# Cart64out_0a.net
KiCad netlist of a schematic drawn in EAGLE
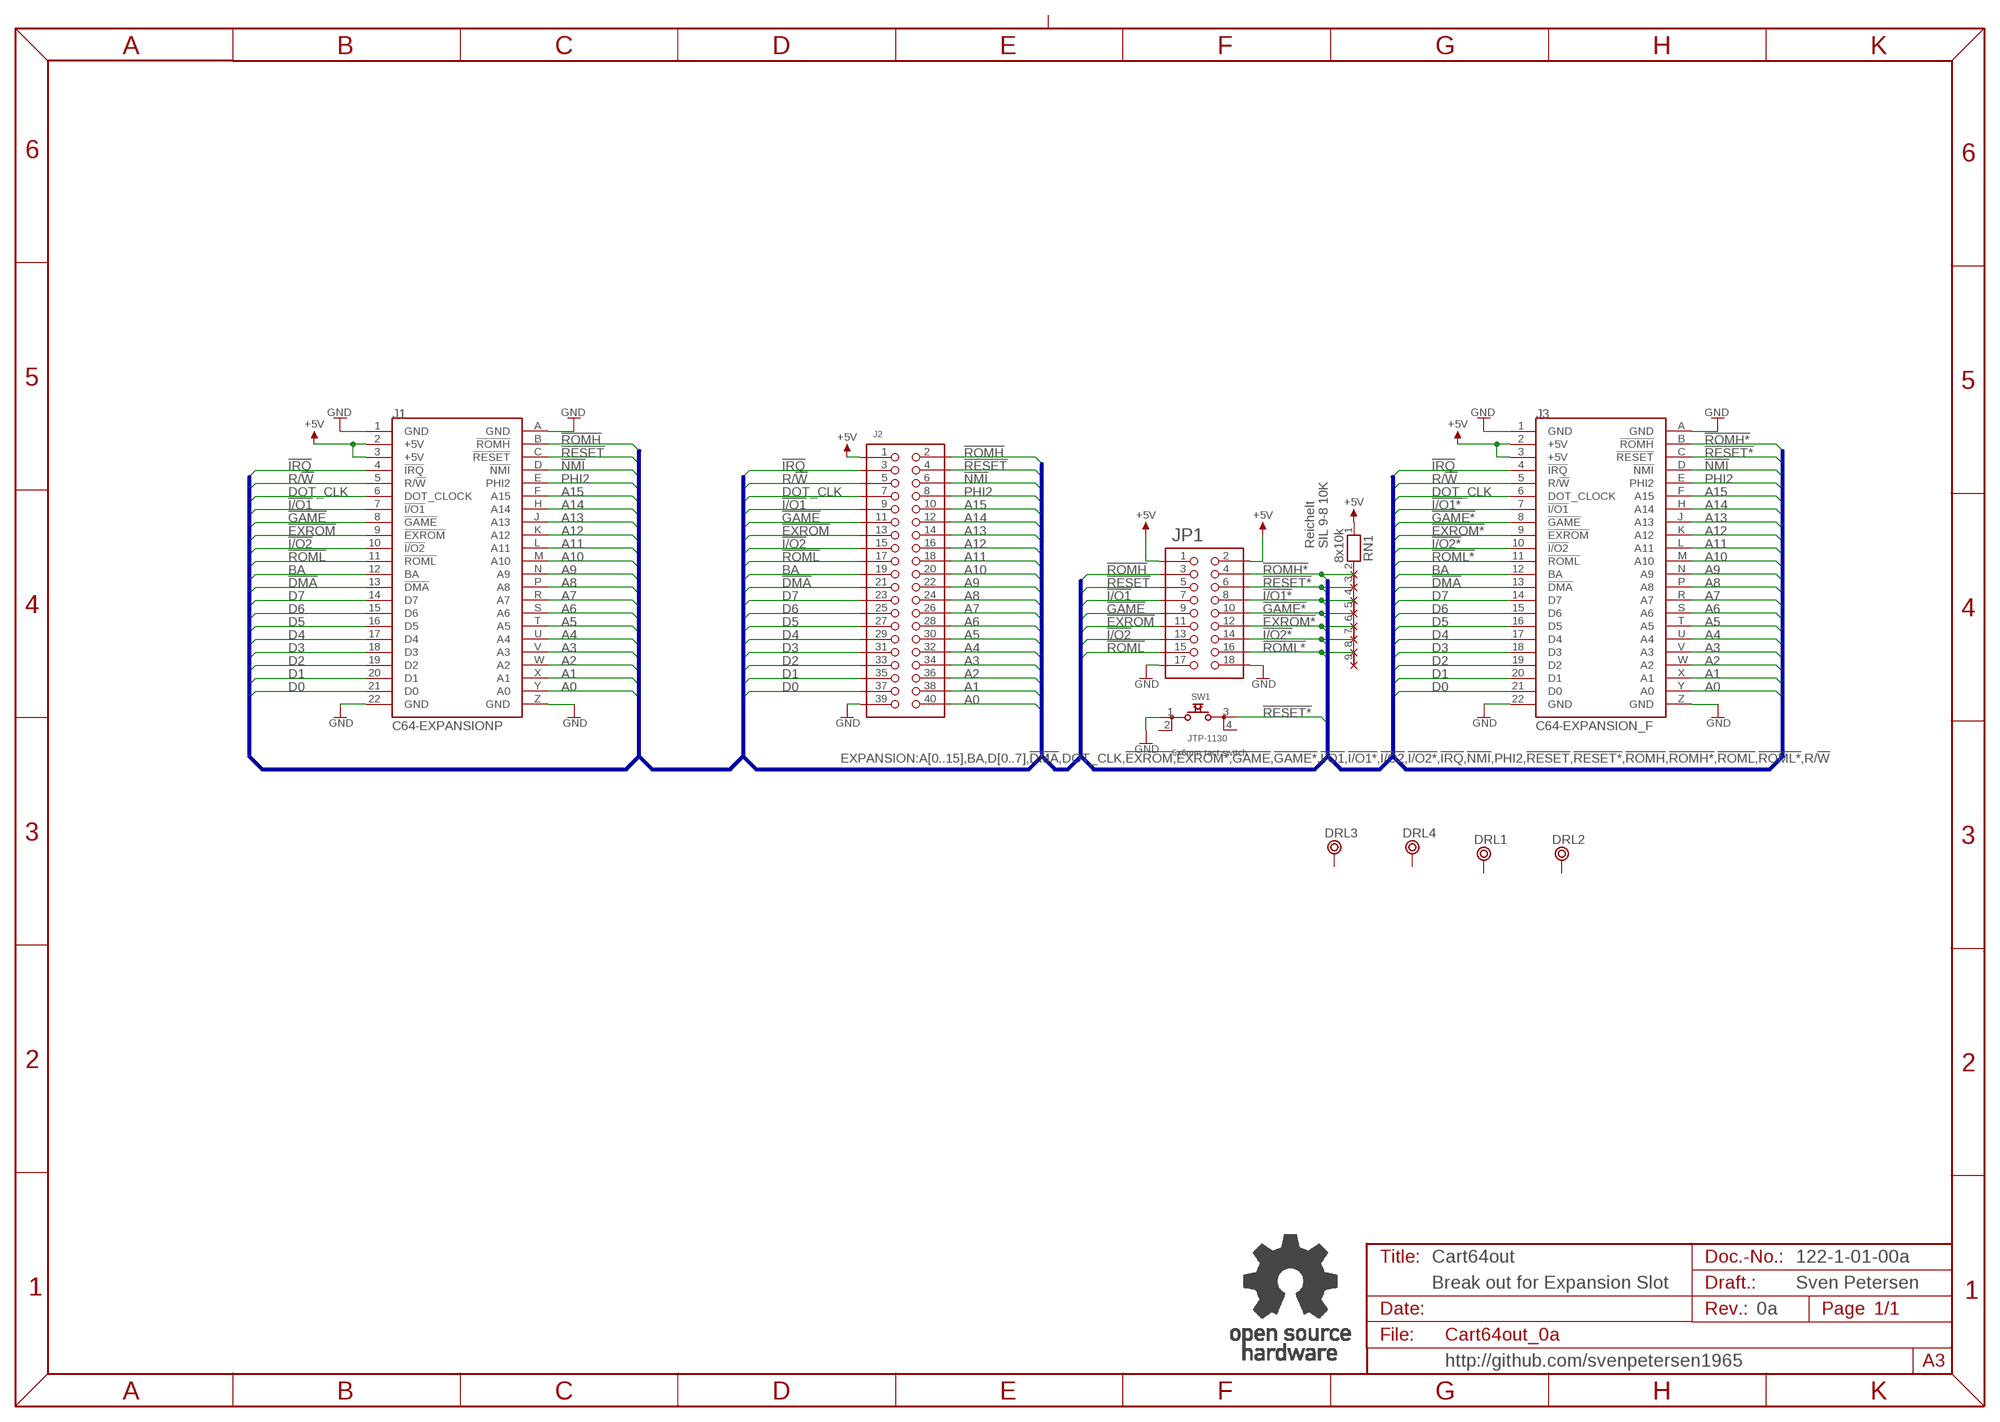
[diagram p0: schematic, sheet 1]

(export (version "E")
  (design (tool "Eeschema 10.0.6"))
  (components
    (comp (ref "DRL1")
      (value "BOHR3,3")
      (footprint "eagle-import:BOHR3,3")
      (libsource (lib "eagle-import") (part "BOHR3,3"))
    )
    (comp (ref "DRL2")
      (value "BOHR3,3")
      (footprint "eagle-import:BOHR3,3")
      (libsource (lib "eagle-import") (part "BOHR3,3"))
    )
    (comp (ref "DRL3")
      (value "BOHR3,3")
      (footprint "eagle-import:BOHR3,3")
      (libsource (lib "eagle-import") (part "BOHR3,3"))
    )
    (comp (ref "DRL4")
      (value "BOHR3,3")
      (footprint "eagle-import:BOHR3,3")
      (libsource (lib "eagle-import") (part "BOHR3,3"))
    )
    (comp (ref "J1")
      (value "C64-EXPANSIONP")
      (footprint "eagle-import:EXPPORT")
      (libsource (lib "eagle-import") (part "C64-EXPANSIONP"))
    )
    (comp (ref "J2")
      (value "PINHD-2X20WV")
      (footprint "eagle-import:2X20WV")
      (libsource (lib "eagle-import") (part "PINHD-2X20WV"))
    )
    (comp (ref "J3")
      (value "C64-EXPANSION_F")
      (footprint "eagle-import:EXPANSION_OUT")
      (libsource (lib "eagle-import") (part "C64-EXPANSION_F"))
    )
    (comp (ref "JP1")
      (value "PINHD-2X9")
      (footprint "eagle-import:2X09")
      (libsource (lib "eagle-import") (part "PINHD-2X9"))
    )
    (comp (ref "RN1")
      (value "8x10k")
      (footprint "eagle-import:RN-9")
      (libsource (lib "eagle-import") (part "RN08"))
    )
    (comp (ref "SW1")
      (value "JTP-1130")
      (footprint "eagle-import:JTP-1130")
      (libsource (lib "eagle-import") (part "JTP-1130"))
    )
    (comp (ref "U$22")
      (value "OPEN_SOURCE_HW")
      (footprint "eagle-import:OPENHW")
      (libsource (lib "eagle-import") (part "OPEN_SOURCE_HW"))
    )
  )
  (nets
    (net (code "1") (name "+5V") (class "Default")
      (node (ref "J1") (pin "2") (pinfunction "+5V_2") (pintype "power_in"))
      (node (ref "J1") (pin "3") (pinfunction "+5V_3") (pintype "power_in"))
      (node (ref "J2") (pin "1") (pinfunction "1_1") (pintype "passive"))
      (node (ref "J3") (pin "2") (pinfunction "+5V_2") (pintype "power_in"))
      (node (ref "J3") (pin "3") (pinfunction "+5V_3") (pintype "power_in"))
      (node (ref "JP1") (pin "1") (pinfunction "1_1") (pintype "passive"))
      (node (ref "JP1") (pin "2") (pinfunction "2_2") (pintype "passive"))
      (node (ref "RN1") (pin "1") (pinfunction "1_1") (pintype "passive"))
    )
    (net (code "2") (name "/A0") (class "Default")
      (node (ref "J1") (pin "Y") (pinfunction "A0_Y") (pintype "bidirectional"))
      (node (ref "J2") (pin "40") (pinfunction "40_40") (pintype "passive"))
      (node (ref "J3") (pin "Y") (pinfunction "A0_Y") (pintype "bidirectional"))
    )
    (net (code "3") (name "/A1") (class "Default")
      (node (ref "J1") (pin "X") (pinfunction "A1_X") (pintype "bidirectional"))
      (node (ref "J2") (pin "38") (pinfunction "38_38") (pintype "passive"))
      (node (ref "J3") (pin "X") (pinfunction "A1_X") (pintype "bidirectional"))
    )
    (net (code "4") (name "/A2") (class "Default")
      (node (ref "J1") (pin "W") (pinfunction "A2_W") (pintype "bidirectional"))
      (node (ref "J2") (pin "36") (pinfunction "36_36") (pintype "passive"))
      (node (ref "J3") (pin "W") (pinfunction "A2_W") (pintype "bidirectional"))
    )
    (net (code "5") (name "/A3") (class "Default")
      (node (ref "J1") (pin "V") (pinfunction "A3_V") (pintype "bidirectional"))
      (node (ref "J2") (pin "34") (pinfunction "34_34") (pintype "passive"))
      (node (ref "J3") (pin "V") (pinfunction "A3_V") (pintype "bidirectional"))
    )
    (net (code "6") (name "/A4") (class "Default")
      (node (ref "J1") (pin "U") (pinfunction "A4_U") (pintype "bidirectional"))
      (node (ref "J2") (pin "32") (pinfunction "32_32") (pintype "passive"))
      (node (ref "J3") (pin "U") (pinfunction "A4_U") (pintype "bidirectional"))
    )
    (net (code "7") (name "/A5") (class "Default")
      (node (ref "J1") (pin "T") (pinfunction "A5_T") (pintype "bidirectional"))
      (node (ref "J2") (pin "30") (pinfunction "30_30") (pintype "passive"))
      (node (ref "J3") (pin "T") (pinfunction "A5_T") (pintype "bidirectional"))
    )
    (net (code "8") (name "/A6") (class "Default")
      (node (ref "J1") (pin "S") (pinfunction "A6_S") (pintype "bidirectional"))
      (node (ref "J2") (pin "28") (pinfunction "28_28") (pintype "passive"))
      (node (ref "J3") (pin "S") (pinfunction "A6_S") (pintype "bidirectional"))
    )
    (net (code "9") (name "/A7") (class "Default")
      (node (ref "J1") (pin "R") (pinfunction "A7_R") (pintype "bidirectional"))
      (node (ref "J2") (pin "26") (pinfunction "26_26") (pintype "passive"))
      (node (ref "J3") (pin "R") (pinfunction "A7_R") (pintype "bidirectional"))
    )
    (net (code "10") (name "/A8") (class "Default")
      (node (ref "J1") (pin "P") (pinfunction "A8_P") (pintype "bidirectional"))
      (node (ref "J2") (pin "24") (pinfunction "24_24") (pintype "passive"))
      (node (ref "J3") (pin "P") (pinfunction "A8_P") (pintype "bidirectional"))
    )
    (net (code "11") (name "/A9") (class "Default")
      (node (ref "J1") (pin "N") (pinfunction "A9_N") (pintype "bidirectional"))
      (node (ref "J2") (pin "22") (pinfunction "22_22") (pintype "passive"))
      (node (ref "J3") (pin "N") (pinfunction "A9_N") (pintype "bidirectional"))
    )
    (net (code "12") (name "/A10") (class "Default")
      (node (ref "J1") (pin "M") (pinfunction "A10_M") (pintype "bidirectional"))
      (node (ref "J2") (pin "20") (pinfunction "20_20") (pintype "passive"))
      (node (ref "J3") (pin "M") (pinfunction "A10_M") (pintype "bidirectional"))
    )
    (net (code "13") (name "/A11") (class "Default")
      (node (ref "J1") (pin "L") (pinfunction "A11_L") (pintype "bidirectional"))
      (node (ref "J2") (pin "18") (pinfunction "18_18") (pintype "passive"))
      (node (ref "J3") (pin "L") (pinfunction "A11_L") (pintype "bidirectional"))
    )
    (net (code "14") (name "/A12") (class "Default")
      (node (ref "J1") (pin "K") (pinfunction "A12_K") (pintype "bidirectional"))
      (node (ref "J2") (pin "16") (pinfunction "16_16") (pintype "passive"))
      (node (ref "J3") (pin "K") (pinfunction "A12_K") (pintype "bidirectional"))
    )
    (net (code "15") (name "/A13") (class "Default")
      (node (ref "J1") (pin "J") (pinfunction "A13_J") (pintype "bidirectional"))
      (node (ref "J2") (pin "14") (pinfunction "14_14") (pintype "passive"))
      (node (ref "J3") (pin "J") (pinfunction "A13_J") (pintype "bidirectional"))
    )
    (net (code "16") (name "/A14") (class "Default")
      (node (ref "J1") (pin "H") (pinfunction "A14_H") (pintype "bidirectional"))
      (node (ref "J2") (pin "12") (pinfunction "12_12") (pintype "passive"))
      (node (ref "J3") (pin "H") (pinfunction "A14_H") (pintype "bidirectional"))
    )
    (net (code "17") (name "/A15") (class "Default")
      (node (ref "J1") (pin "F") (pinfunction "A15_F") (pintype "bidirectional"))
      (node (ref "J2") (pin "10") (pinfunction "10_10") (pintype "passive"))
      (node (ref "J3") (pin "F") (pinfunction "A15_F") (pintype "bidirectional"))
    )
    (net (code "18") (name "/BA") (class "Default")
      (node (ref "J1") (pin "12") (pinfunction "BA_12") (pintype "output"))
      (node (ref "J2") (pin "19") (pinfunction "19_19") (pintype "passive"))
      (node (ref "J3") (pin "12") (pinfunction "BA_12") (pintype "output"))
    )
    (net (code "19") (name "/D0") (class "Default")
      (node (ref "J1") (pin "21") (pinfunction "D0_21") (pintype "bidirectional"))
      (node (ref "J2") (pin "37") (pinfunction "37_37") (pintype "passive"))
      (node (ref "J3") (pin "21") (pinfunction "D0_21") (pintype "bidirectional"))
    )
    (net (code "20") (name "/D1") (class "Default")
      (node (ref "J1") (pin "20") (pinfunction "D1_20") (pintype "bidirectional"))
      (node (ref "J2") (pin "35") (pinfunction "35_35") (pintype "passive"))
      (node (ref "J3") (pin "20") (pinfunction "D1_20") (pintype "bidirectional"))
    )
    (net (code "21") (name "/D2") (class "Default")
      (node (ref "J1") (pin "19") (pinfunction "D2_19") (pintype "bidirectional"))
      (node (ref "J2") (pin "33") (pinfunction "33_33") (pintype "passive"))
      (node (ref "J3") (pin "19") (pinfunction "D2_19") (pintype "bidirectional"))
    )
    (net (code "22") (name "/D3") (class "Default")
      (node (ref "J1") (pin "18") (pinfunction "D3_18") (pintype "bidirectional"))
      (node (ref "J2") (pin "31") (pinfunction "31_31") (pintype "passive"))
      (node (ref "J3") (pin "18") (pinfunction "D3_18") (pintype "bidirectional"))
    )
    (net (code "23") (name "/D4") (class "Default")
      (node (ref "J1") (pin "17") (pinfunction "D4_17") (pintype "bidirectional"))
      (node (ref "J2") (pin "29") (pinfunction "29_29") (pintype "passive"))
      (node (ref "J3") (pin "17") (pinfunction "D4_17") (pintype "bidirectional"))
    )
    (net (code "24") (name "/D5") (class "Default")
      (node (ref "J1") (pin "16") (pinfunction "D5_16") (pintype "bidirectional"))
      (node (ref "J2") (pin "27") (pinfunction "27_27") (pintype "passive"))
      (node (ref "J3") (pin "16") (pinfunction "D5_16") (pintype "bidirectional"))
    )
    (net (code "25") (name "/D6") (class "Default")
      (node (ref "J1") (pin "15") (pinfunction "D6_15") (pintype "bidirectional"))
      (node (ref "J2") (pin "25") (pinfunction "25_25") (pintype "passive"))
      (node (ref "J3") (pin "15") (pinfunction "D6_15") (pintype "bidirectional"))
    )
    (net (code "26") (name "/D7") (class "Default")
      (node (ref "J1") (pin "14") (pinfunction "D7_14") (pintype "bidirectional"))
      (node (ref "J2") (pin "23") (pinfunction "23_23") (pintype "passive"))
      (node (ref "J3") (pin "14") (pinfunction "D7_14") (pintype "bidirectional"))
    )
    (net (code "27") (name "/DOT_CLK") (class "Default")
      (node (ref "J1") (pin "6") (pinfunction "DOT_CLOCK_6") (pintype "output"))
      (node (ref "J2") (pin "7") (pinfunction "7_7") (pintype "passive"))
      (node (ref "J3") (pin "6") (pinfunction "DOT_CLOCK_6") (pintype "output"))
    )
    (net (code "28") (name "/PHI2") (class "Default")
      (node (ref "J1") (pin "E") (pinfunction "PHI2_E") (pintype "output"))
      (node (ref "J2") (pin "8") (pinfunction "8_8") (pintype "passive"))
      (node (ref "J3") (pin "E") (pinfunction "PHI2_E") (pintype "output"))
    )
    (net (code "29") (name "/R{slash}~{W}") (class "Default")
      (node (ref "J1") (pin "5") (pinfunction "R/~{W}_5") (pintype "output"))
      (node (ref "J2") (pin "5") (pinfunction "5_5") (pintype "passive"))
      (node (ref "J3") (pin "5") (pinfunction "R/~{W}_5") (pintype "output"))
    )
    (net (code "31") (name "/~{DMA}") (class "Default")
      (node (ref "J1") (pin "13") (pinfunction "~{DMA}_13") (pintype "input"))
      (node (ref "J2") (pin "21") (pinfunction "21_21") (pintype "passive"))
      (node (ref "J3") (pin "13") (pinfunction "~{DMA}_13") (pintype "input"))
    )
    (net (code "32") (name "/~{EXROM*}") (class "Default")
      (node (ref "J3") (pin "9") (pinfunction "~{EXROM}_9") (pintype "input"))
      (node (ref "JP1") (pin "12") (pinfunction "12_12") (pintype "passive"))
      (node (ref "RN1") (pin "6") (pinfunction "6_6") (pintype "passive"))
    )
    (net (code "33") (name "/~{EXROM}") (class "Default")
      (node (ref "J1") (pin "9") (pinfunction "~{EXROM}_9") (pintype "input"))
      (node (ref "J2") (pin "13") (pinfunction "13_13") (pintype "passive"))
      (node (ref "JP1") (pin "11") (pinfunction "11_11") (pintype "passive"))
    )
    (net (code "34") (name "/~{GAME*}") (class "Default")
      (node (ref "J3") (pin "8") (pinfunction "~{GAME}_8") (pintype "input"))
      (node (ref "JP1") (pin "10") (pinfunction "10_10") (pintype "passive"))
      (node (ref "RN1") (pin "5") (pinfunction "5_5") (pintype "passive"))
    )
    (net (code "35") (name "/~{GAME}") (class "Default")
      (node (ref "J1") (pin "8") (pinfunction "~{GAME}_8") (pintype "input"))
      (node (ref "J2") (pin "11") (pinfunction "11_11") (pintype "passive"))
      (node (ref "JP1") (pin "9") (pinfunction "9_9") (pintype "passive"))
    )
    (net (code "36") (name "/~{IRQ}") (class "Default")
      (node (ref "J1") (pin "4") (pinfunction "~{IRQ}_4") (pintype "input"))
      (node (ref "J2") (pin "3") (pinfunction "3_3") (pintype "passive"))
      (node (ref "J3") (pin "4") (pinfunction "~{IRQ}_4") (pintype "input"))
    )
    (net (code "37") (name "/~{I{slash}O1*}") (class "Default")
      (node (ref "J3") (pin "7") (pinfunction "~{I/O1}_7") (pintype "output"))
      (node (ref "JP1") (pin "8") (pinfunction "8_8") (pintype "passive"))
      (node (ref "RN1") (pin "4") (pinfunction "4_4") (pintype "passive"))
    )
    (net (code "38") (name "/~{I{slash}O1}") (class "Default")
      (node (ref "J1") (pin "7") (pinfunction "~{I/O1}_7") (pintype "output"))
      (node (ref "J2") (pin "9") (pinfunction "9_9") (pintype "passive"))
      (node (ref "JP1") (pin "7") (pinfunction "7_7") (pintype "passive"))
    )
    (net (code "39") (name "/~{I{slash}O2*}") (class "Default")
      (node (ref "J3") (pin "10") (pinfunction "~{I/O2}_10") (pintype "output"))
      (node (ref "JP1") (pin "14") (pinfunction "14_14") (pintype "passive"))
      (node (ref "RN1") (pin "7") (pinfunction "7_7") (pintype "passive"))
    )
    (net (code "40") (name "/~{I{slash}O2}") (class "Default")
      (node (ref "J1") (pin "10") (pinfunction "~{I/O2}_10") (pintype "output"))
      (node (ref "J2") (pin "15") (pinfunction "15_15") (pintype "passive"))
      (node (ref "JP1") (pin "13") (pinfunction "13_13") (pintype "passive"))
    )
    (net (code "41") (name "/~{NMI}") (class "Default")
      (node (ref "J1") (pin "D") (pinfunction "~{NMI}_D") (pintype "input"))
      (node (ref "J2") (pin "6") (pinfunction "6_6") (pintype "passive"))
      (node (ref "J3") (pin "D") (pinfunction "~{NMI}_D") (pintype "input"))
    )
    (net (code "42") (name "/~{RESET*}") (class "Default")
      (node (ref "J3") (pin "C") (pinfunction "~{RESET}_C") (pintype "open_collector"))
      (node (ref "JP1") (pin "6") (pinfunction "6_6") (pintype "passive"))
      (node (ref "RN1") (pin "3") (pinfunction "3_3") (pintype "passive"))
      (node (ref "SW1") (pin "3") (pinfunction "3_3") (pintype "passive"))
    )
    (net (code "43") (name "/~{RESET}") (class "Default")
      (node (ref "J1") (pin "C") (pinfunction "~{RESET}_C") (pintype "open_collector"))
      (node (ref "J2") (pin "4") (pinfunction "4_4") (pintype "passive"))
      (node (ref "JP1") (pin "5") (pinfunction "5_5") (pintype "passive"))
    )
    (net (code "44") (name "/~{ROMH*}") (class "Default")
      (node (ref "J3") (pin "B") (pinfunction "~{ROMH}_B") (pintype "output"))
      (node (ref "JP1") (pin "4") (pinfunction "4_4") (pintype "passive"))
      (node (ref "RN1") (pin "2") (pinfunction "2_2") (pintype "passive"))
    )
    (net (code "45") (name "/~{ROMH}") (class "Default")
      (node (ref "J1") (pin "B") (pinfunction "~{ROMH}_B") (pintype "output"))
      (node (ref "J2") (pin "2") (pinfunction "2_2") (pintype "passive"))
      (node (ref "JP1") (pin "3") (pinfunction "3_3") (pintype "passive"))
    )
    (net (code "46") (name "/~{ROML*}") (class "Default")
      (node (ref "J3") (pin "11") (pinfunction "~{ROML}_11") (pintype "output"))
      (node (ref "JP1") (pin "16") (pinfunction "16_16") (pintype "passive"))
      (node (ref "RN1") (pin "8") (pinfunction "8_8") (pintype "passive"))
    )
    (net (code "47") (name "/~{ROML}") (class "Default")
      (node (ref "J1") (pin "11") (pinfunction "~{ROML}_11") (pintype "output"))
      (node (ref "J2") (pin "17") (pinfunction "17_17") (pintype "passive"))
      (node (ref "JP1") (pin "15") (pinfunction "15_15") (pintype "passive"))
    )
    (net (code "48") (name "GND") (class "Default")
      (node (ref "J1") (pin "1") (pinfunction "GND_1") (pintype "power_in"))
      (node (ref "J1") (pin "22") (pinfunction "GND_22") (pintype "power_in"))
      (node (ref "J1") (pin "A") (pinfunction "GND_A") (pintype "power_in"))
      (node (ref "J1") (pin "Z") (pinfunction "GND_Z") (pintype "power_in"))
      (node (ref "J2") (pin "39") (pinfunction "39_39") (pintype "passive"))
      (node (ref "J3") (pin "1") (pinfunction "GND_1") (pintype "power_in"))
      (node (ref "J3") (pin "22") (pinfunction "GND_22") (pintype "power_in"))
      (node (ref "J3") (pin "A") (pinfunction "GND_A") (pintype "power_in"))
      (node (ref "J3") (pin "Z") (pinfunction "GND_Z") (pintype "power_in"))
      (node (ref "JP1") (pin "17") (pinfunction "17_17") (pintype "passive"))
      (node (ref "JP1") (pin "18") (pinfunction "18_18") (pintype "passive"))
      (node (ref "SW1") (pin "1") (pinfunction "1_1") (pintype "passive"))
    )
    (net (code "49") (name "unconnected-(DRL1-PadP$1)") (class "Default")
      (node (ref "DRL1") (pin "P$1") (pinfunction "P$1_P$1") (pintype "passive"))
    )
    (net (code "50") (name "unconnected-(DRL2-PadP$1)") (class "Default")
      (node (ref "DRL2") (pin "P$1") (pinfunction "P$1_P$1") (pintype "passive"))
    )
    (net (code "51") (name "unconnected-(DRL3-PadP$1)") (class "Default")
      (node (ref "DRL3") (pin "P$1") (pinfunction "P$1_P$1") (pintype "passive"))
    )
    (net (code "52") (name "unconnected-(DRL4-PadP$1)") (class "Default")
      (node (ref "DRL4") (pin "P$1") (pinfunction "P$1_P$1") (pintype "passive"))
    )
    (net (code "53") (name "unconnected-(RN1-Pad9)") (class "Default")
      (node (ref "RN1") (pin "9") (pinfunction "9_9") (pintype "passive"))
    )
    (net (code "54") (name "unconnected-(SW1-Pad2)") (class "Default")
      (node (ref "SW1") (pin "2") (pinfunction "2_2") (pintype "passive"))
    )
    (net (code "55") (name "unconnected-(SW1-Pad4)") (class "Default")
      (node (ref "SW1") (pin "4") (pinfunction "4_4") (pintype "passive"))
    )
  )
)
